# ssm.net
KiCad netlist of a schematic drawn in EAGLE
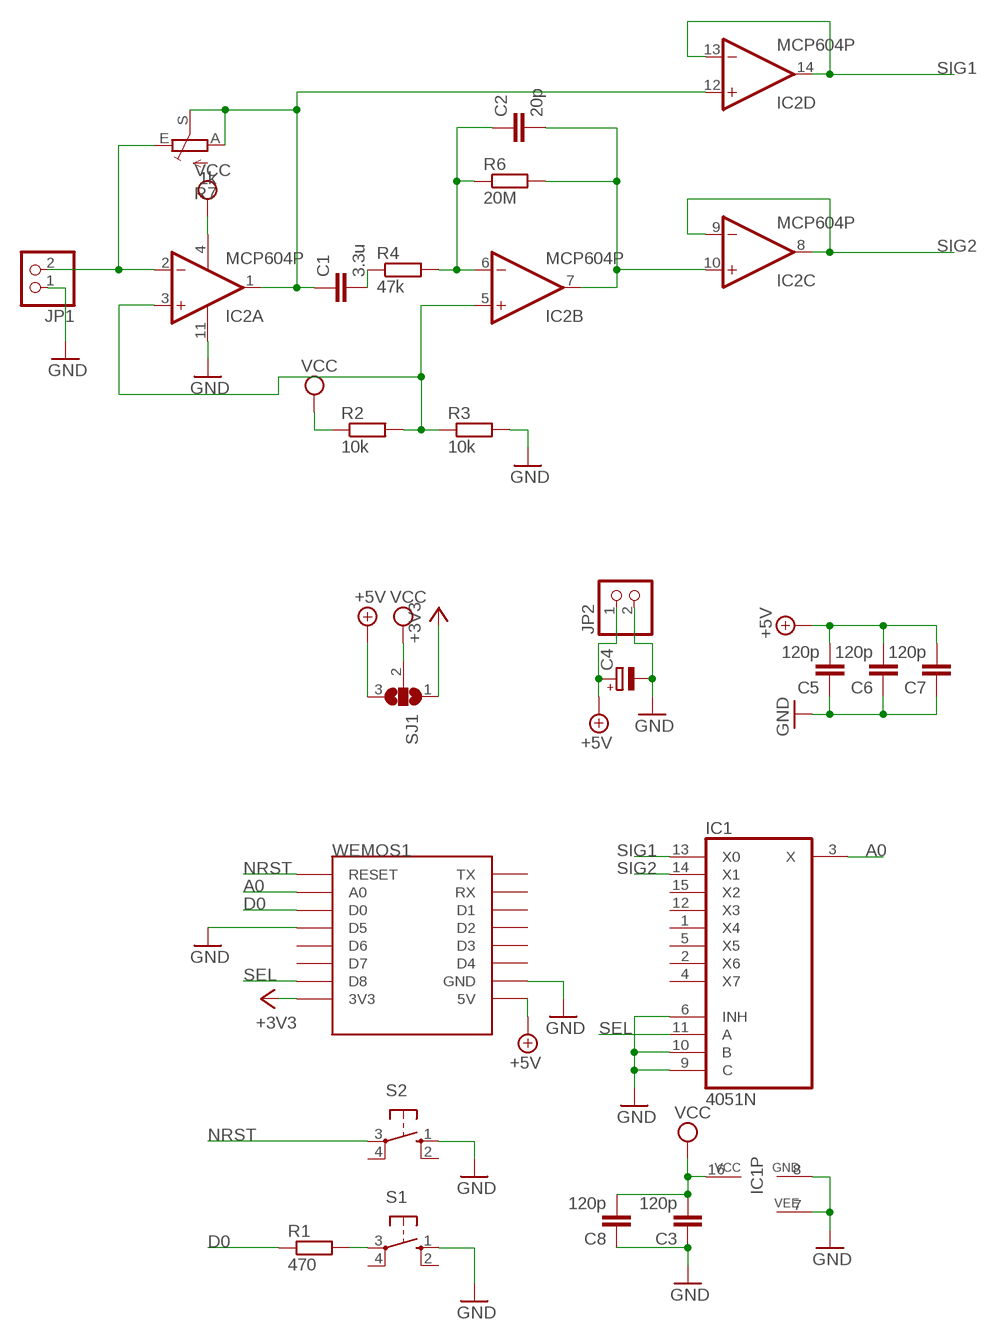
[diagram p0: schematic, sheet 1]

(export (version "E")
  (design (tool "Eeschema 10.0.6"))
  (components
    (comp (ref "C1")
      (value "3.3u")
      (footprint "eagle-import:C225-087X210")
      (libsource (lib "eagle-import") (part "C-EU"))
    )
    (comp (ref "C2")
      (value "20p")
      (footprint "eagle-import:C025-024X044")
      (libsource (lib "eagle-import") (part "C-EU025-024X044"))
    )
    (comp (ref "C3")
      (value "120p")
      (footprint "eagle-import:C025-024X044")
      (libsource (lib "eagle-import") (part "C-EU025-024X044"))
    )
    (comp (ref "C4")
      (value "CPOL-EUE2.5-5")
      (footprint "eagle-import:E2,5-5")
      (libsource (lib "eagle-import") (part "CPOL-EUE2.5-5"))
    )
    (comp (ref "C5")
      (value "120p")
      (footprint "eagle-import:C025-024X044")
      (libsource (lib "eagle-import") (part "C-EU025-024X044"))
    )
    (comp (ref "C6")
      (value "120p")
      (footprint "eagle-import:C025-024X044")
      (libsource (lib "eagle-import") (part "C-EU025-024X044"))
    )
    (comp (ref "C7")
      (value "120p")
      (footprint "eagle-import:C025-024X044")
      (libsource (lib "eagle-import") (part "C-EU025-024X044"))
    )
    (comp (ref "C8")
      (value "120p")
      (footprint "eagle-import:C025-024X044")
      (libsource (lib "eagle-import") (part "C-EU025-024X044"))
    )
    (comp (ref "IC1")
      (value "4051N")
      (footprint "eagle-import:DIL16")
      (libsource (lib "eagle-import") (part "4051N"))
    )
    (comp (ref "IC2")
      (value "MCP604P")
      (footprint "eagle-import:DIL14")
      (libsource (lib "eagle-import") (part "MCP604P"))
    )
    (comp (ref "JP1")
      (value "PINHD-1X2")
      (footprint "eagle-import:1X02")
      (libsource (lib "eagle-import") (part "PINHD-1X2"))
    )
    (comp (ref "JP2")
      (value "PINHD-1X2")
      (footprint "eagle-import:1X02")
      (libsource (lib "eagle-import") (part "PINHD-1X2"))
    )
    (comp (ref "R1")
      (value "470")
      (footprint "eagle-import:0204_7")
      (libsource (lib "eagle-import") (part "resistor_348_R-EU_0204/7"))
    )
    (comp (ref "R2")
      (value "10k")
      (footprint "eagle-import:0204_7")
      (libsource (lib "eagle-import") (part "resistor_348_R-EU_0204/7"))
    )
    (comp (ref "R3")
      (value "10k")
      (footprint "eagle-import:0204_7")
      (libsource (lib "eagle-import") (part "resistor_348_R-EU_0204/7"))
    )
    (comp (ref "R4")
      (value "47k")
      (footprint "eagle-import:0204_7")
      (libsource (lib "eagle-import") (part "resistor_348_R-EU_0204/7"))
    )
    (comp (ref "R6")
      (value "20M")
      (footprint "eagle-import:0207_10")
      (libsource (lib "eagle-import") (part "R-EU_0207/10"))
    )
    (comp (ref "R7")
      (value "1k")
      (footprint "eagle-import:B64Y")
      (libsource (lib "eagle-import") (part "TRIM_EU-B64Y"))
    )
    (comp (ref "S1")
      (value "10-XX")
      (footprint "eagle-import:B3F-10XX")
      (fields (field (name "MPN") "B3F-1000"))
      (libsource (lib "eagle-import") (part "10-XX"))
    )
    (comp (ref "S2")
      (value "10-XX")
      (footprint "eagle-import:B3F-10XX")
      (fields (field (name "MPN") "B3F-1000"))
      (libsource (lib "eagle-import") (part "10-XX"))
    )
    (comp (ref "SJ1")
      (value "SJ2W")
      (footprint "eagle-import:SJ_2")
      (libsource (lib "eagle-import") (part "SJ2W"))
    )
    (comp (ref "WEMOS1")
      (value "WEMOS-D1-MINI")
      (footprint "eagle-import:WEMOS-D1-MINI")
      (libsource (lib "eagle-import") (part "WEMOS-D1-MINI"))
    )
  )
  (nets
    (net (code "1") (name "+3V3") (class "Default")
      (node (ref "SJ1") (pin "1") (pinfunction "1_1") (pintype "passive"))
      (node (ref "WEMOS1") (pin "3V3") (pinfunction "3V3_3V3") (pintype "bidirectional"))
    )
    (net (code "2") (name "+5V") (class "Default")
      (node (ref "C4") (pin "+") (pinfunction "+_+") (pintype "passive"))
      (node (ref "C5") (pin "2") (pinfunction "2_2") (pintype "passive"))
      (node (ref "C6") (pin "2") (pinfunction "2_2") (pintype "passive"))
      (node (ref "C7") (pin "2") (pinfunction "2_2") (pintype "passive"))
      (node (ref "JP2") (pin "1") (pinfunction "1_1") (pintype "passive"))
      (node (ref "SJ1") (pin "3") (pinfunction "3_3") (pintype "passive"))
      (node (ref "WEMOS1") (pin "5V") (pinfunction "5V_5V") (pintype "bidirectional"))
    )
    (net (code "3") (name "/A0") (class "Default")
      (node (ref "IC1") (pin "3") (pinfunction "X_3") (pintype "bidirectional"))
      (node (ref "WEMOS1") (pin "A0") (pinfunction "A0_A0") (pintype "bidirectional"))
    )
    (net (code "4") (name "/D0") (class "Default")
      (node (ref "R1") (pin "1") (pinfunction "1_1") (pintype "passive"))
      (node (ref "WEMOS1") (pin "D0") (pinfunction "D0_D0") (pintype "bidirectional"))
    )
    (net (code "5") (name "/NRST") (class "Default")
      (node (ref "S2") (pin "3") (pinfunction "P_3") (pintype "passive"))
      (node (ref "WEMOS1") (pin "RESET") (pinfunction "RESET_RESET") (pintype "bidirectional"))
    )
    (net (code "6") (name "/SEL") (class "Default")
      (node (ref "IC1") (pin "11") (pinfunction "A_11") (pintype "input"))
      (node (ref "WEMOS1") (pin "D8") (pinfunction "D8_D8") (pintype "bidirectional"))
    )
    (net (code "7") (name "/SIG1") (class "Default")
      (node (ref "IC1") (pin "13") (pinfunction "X0_13") (pintype "bidirectional"))
      (node (ref "IC2") (pin "13") (pinfunction "-IN_13") (pintype "input"))
      (node (ref "IC2") (pin "14") (pinfunction "OUT_14") (pintype "output"))
    )
    (net (code "8") (name "/SIG2") (class "Default")
      (node (ref "IC1") (pin "14") (pinfunction "X1_14") (pintype "bidirectional"))
      (node (ref "IC2") (pin "8") (pinfunction "OUT_8") (pintype "output"))
      (node (ref "IC2") (pin "9") (pinfunction "-IN_9") (pintype "input"))
    )
    (net (code "9") (name "GND") (class "Default")
      (node (ref "C3") (pin "1") (pinfunction "1_1") (pintype "passive"))
      (node (ref "C4") (pin "-") (pinfunction "-_-") (pintype "passive"))
      (node (ref "C5") (pin "1") (pinfunction "1_1") (pintype "passive"))
      (node (ref "C6") (pin "1") (pinfunction "1_1") (pintype "passive"))
      (node (ref "C7") (pin "1") (pinfunction "1_1") (pintype "passive"))
      (node (ref "C8") (pin "1") (pinfunction "1_1") (pintype "passive"))
      (node (ref "IC1") (pin "10") (pinfunction "B_10") (pintype "input"))
      (node (ref "IC1") (pin "6") (pinfunction "INH_6") (pintype "input"))
      (node (ref "IC1") (pin "7") (pinfunction "VEE_7") (pintype "power_in"))
      (node (ref "IC1") (pin "8") (pinfunction "GND_8") (pintype "power_in"))
      (node (ref "IC1") (pin "9") (pinfunction "C_9") (pintype "input"))
      (node (ref "IC2") (pin "11") (pinfunction "V-_11") (pintype "power_in"))
      (node (ref "JP1") (pin "1") (pinfunction "1_1") (pintype "passive"))
      (node (ref "JP2") (pin "2") (pinfunction "2_2") (pintype "passive"))
      (node (ref "R3") (pin "2") (pinfunction "2_2") (pintype "passive"))
      (node (ref "S1") (pin "1") (pinfunction "S_1") (pintype "passive"))
      (node (ref "S2") (pin "1") (pinfunction "S_1") (pintype "passive"))
      (node (ref "WEMOS1") (pin "D5") (pinfunction "D5_D5") (pintype "bidirectional"))
      (node (ref "WEMOS1") (pin "GND") (pinfunction "GND_GND") (pintype "bidirectional"))
    )
    (net (code "10") (name "Net-(C1-Pad2)") (class "Default")
      (node (ref "C1") (pin "2") (pinfunction "2_2") (pintype "passive"))
      (node (ref "R4") (pin "1") (pinfunction "1_1") (pintype "passive"))
    )
    (net (code "11") (name "Net-(IC2A-+IN)") (class "Default")
      (node (ref "IC2") (pin "3") (pinfunction "+IN_3") (pintype "input"))
      (node (ref "IC2") (pin "5") (pinfunction "+IN_5") (pintype "input"))
      (node (ref "R2") (pin "2") (pinfunction "2_2") (pintype "passive"))
      (node (ref "R3") (pin "1") (pinfunction "1_1") (pintype "passive"))
    )
    (net (code "12") (name "Net-(IC2A--IN)") (class "Default")
      (node (ref "IC2") (pin "2") (pinfunction "-IN_2") (pintype "input"))
      (node (ref "JP1") (pin "2") (pinfunction "2_2") (pintype "passive"))
      (node (ref "R7") (pin "E") (pinfunction "E_E") (pintype "passive"))
    )
    (net (code "13") (name "Net-(IC2A-OUT)") (class "Default")
      (node (ref "C1") (pin "1") (pinfunction "1_1") (pintype "passive"))
      (node (ref "IC2") (pin "1") (pinfunction "OUT_1") (pintype "output"))
      (node (ref "IC2") (pin "12") (pinfunction "+IN_12") (pintype "input"))
      (node (ref "R7") (pin "A") (pinfunction "A_A") (pintype "passive"))
      (node (ref "R7") (pin "S") (pinfunction "S_S") (pintype "passive"))
    )
    (net (code "14") (name "Net-(IC2B--IN)") (class "Default")
      (node (ref "C2") (pin "1") (pinfunction "1_1") (pintype "passive"))
      (node (ref "IC2") (pin "6") (pinfunction "-IN_6") (pintype "input"))
      (node (ref "R4") (pin "2") (pinfunction "2_2") (pintype "passive"))
      (node (ref "R6") (pin "1") (pinfunction "1_1") (pintype "passive"))
    )
    (net (code "15") (name "Net-(IC2B-OUT)") (class "Default")
      (node (ref "C2") (pin "2") (pinfunction "2_2") (pintype "passive"))
      (node (ref "IC2") (pin "10") (pinfunction "+IN_10") (pintype "input"))
      (node (ref "IC2") (pin "7") (pinfunction "OUT_7") (pintype "output"))
      (node (ref "R6") (pin "2") (pinfunction "2_2") (pintype "passive"))
    )
    (net (code "16") (name "Net-(S1-P)") (class "Default")
      (node (ref "R1") (pin "2") (pinfunction "2_2") (pintype "passive"))
      (node (ref "S1") (pin "3") (pinfunction "P_3") (pintype "passive"))
    )
    (net (code "17") (name "VCC") (class "Default")
      (node (ref "C3") (pin "2") (pinfunction "2_2") (pintype "passive"))
      (node (ref "C8") (pin "2") (pinfunction "2_2") (pintype "passive"))
      (node (ref "IC1") (pin "16") (pinfunction "VCC_16") (pintype "power_in"))
      (node (ref "IC2") (pin "4") (pinfunction "V+_4") (pintype "power_in"))
      (node (ref "R2") (pin "1") (pinfunction "1_1") (pintype "passive"))
      (node (ref "SJ1") (pin "2") (pinfunction "2_2") (pintype "passive"))
    )
    (net (code "18") (name "unconnected-(IC1A-X2-Pad15)") (class "Default")
      (node (ref "IC1") (pin "15") (pinfunction "X2_15") (pintype "bidirectional"))
    )
    (net (code "19") (name "unconnected-(IC1A-X3-Pad12)") (class "Default")
      (node (ref "IC1") (pin "12") (pinfunction "X3_12") (pintype "bidirectional"))
    )
    (net (code "20") (name "unconnected-(IC1A-X4-Pad1)") (class "Default")
      (node (ref "IC1") (pin "1") (pinfunction "X4_1") (pintype "bidirectional"))
    )
    (net (code "21") (name "unconnected-(IC1A-X5-Pad5)") (class "Default")
      (node (ref "IC1") (pin "5") (pinfunction "X5_5") (pintype "bidirectional"))
    )
    (net (code "22") (name "unconnected-(IC1A-X6-Pad2)") (class "Default")
      (node (ref "IC1") (pin "2") (pinfunction "X6_2") (pintype "bidirectional"))
    )
    (net (code "23") (name "unconnected-(IC1A-X7-Pad4)") (class "Default")
      (node (ref "IC1") (pin "4") (pinfunction "X7_4") (pintype "bidirectional"))
    )
    (net (code "24") (name "unconnected-(S1-P1-Pad4)") (class "Default")
      (node (ref "S1") (pin "4") (pinfunction "P1_4") (pintype "passive"))
    )
    (net (code "25") (name "unconnected-(S1-S1-Pad2)") (class "Default")
      (node (ref "S1") (pin "2") (pinfunction "S1_2") (pintype "passive"))
    )
    (net (code "26") (name "unconnected-(S2-P1-Pad4)") (class "Default")
      (node (ref "S2") (pin "4") (pinfunction "P1_4") (pintype "passive"))
    )
    (net (code "27") (name "unconnected-(S2-S1-Pad2)") (class "Default")
      (node (ref "S2") (pin "2") (pinfunction "S1_2") (pintype "passive"))
    )
    (net (code "28") (name "unconnected-(WEMOS1-PadD1)") (class "Default")
      (node (ref "WEMOS1") (pin "D1") (pinfunction "D1_D1") (pintype "bidirectional"))
    )
    (net (code "29") (name "unconnected-(WEMOS1-PadD2)") (class "Default")
      (node (ref "WEMOS1") (pin "D2") (pinfunction "D2_D2") (pintype "bidirectional"))
    )
    (net (code "30") (name "unconnected-(WEMOS1-PadD3)") (class "Default")
      (node (ref "WEMOS1") (pin "D3") (pinfunction "D3_D3") (pintype "bidirectional"))
    )
    (net (code "31") (name "unconnected-(WEMOS1-PadD4)") (class "Default")
      (node (ref "WEMOS1") (pin "D4") (pinfunction "D4_D4") (pintype "bidirectional"))
    )
    (net (code "32") (name "unconnected-(WEMOS1-PadD6)") (class "Default")
      (node (ref "WEMOS1") (pin "D6") (pinfunction "D6_D6") (pintype "bidirectional"))
    )
    (net (code "33") (name "unconnected-(WEMOS1-PadD7)") (class "Default")
      (node (ref "WEMOS1") (pin "D7") (pinfunction "D7_D7") (pintype "bidirectional"))
    )
    (net (code "34") (name "unconnected-(WEMOS1-PadRX)") (class "Default")
      (node (ref "WEMOS1") (pin "RX") (pinfunction "RX_RX") (pintype "bidirectional"))
    )
    (net (code "35") (name "unconnected-(WEMOS1-PadTX)") (class "Default")
      (node (ref "WEMOS1") (pin "TX") (pinfunction "TX_TX") (pintype "bidirectional"))
    )
  )
)
